# usb_interface.net
KiCad netlist of a schematic drawn in Altium Designer
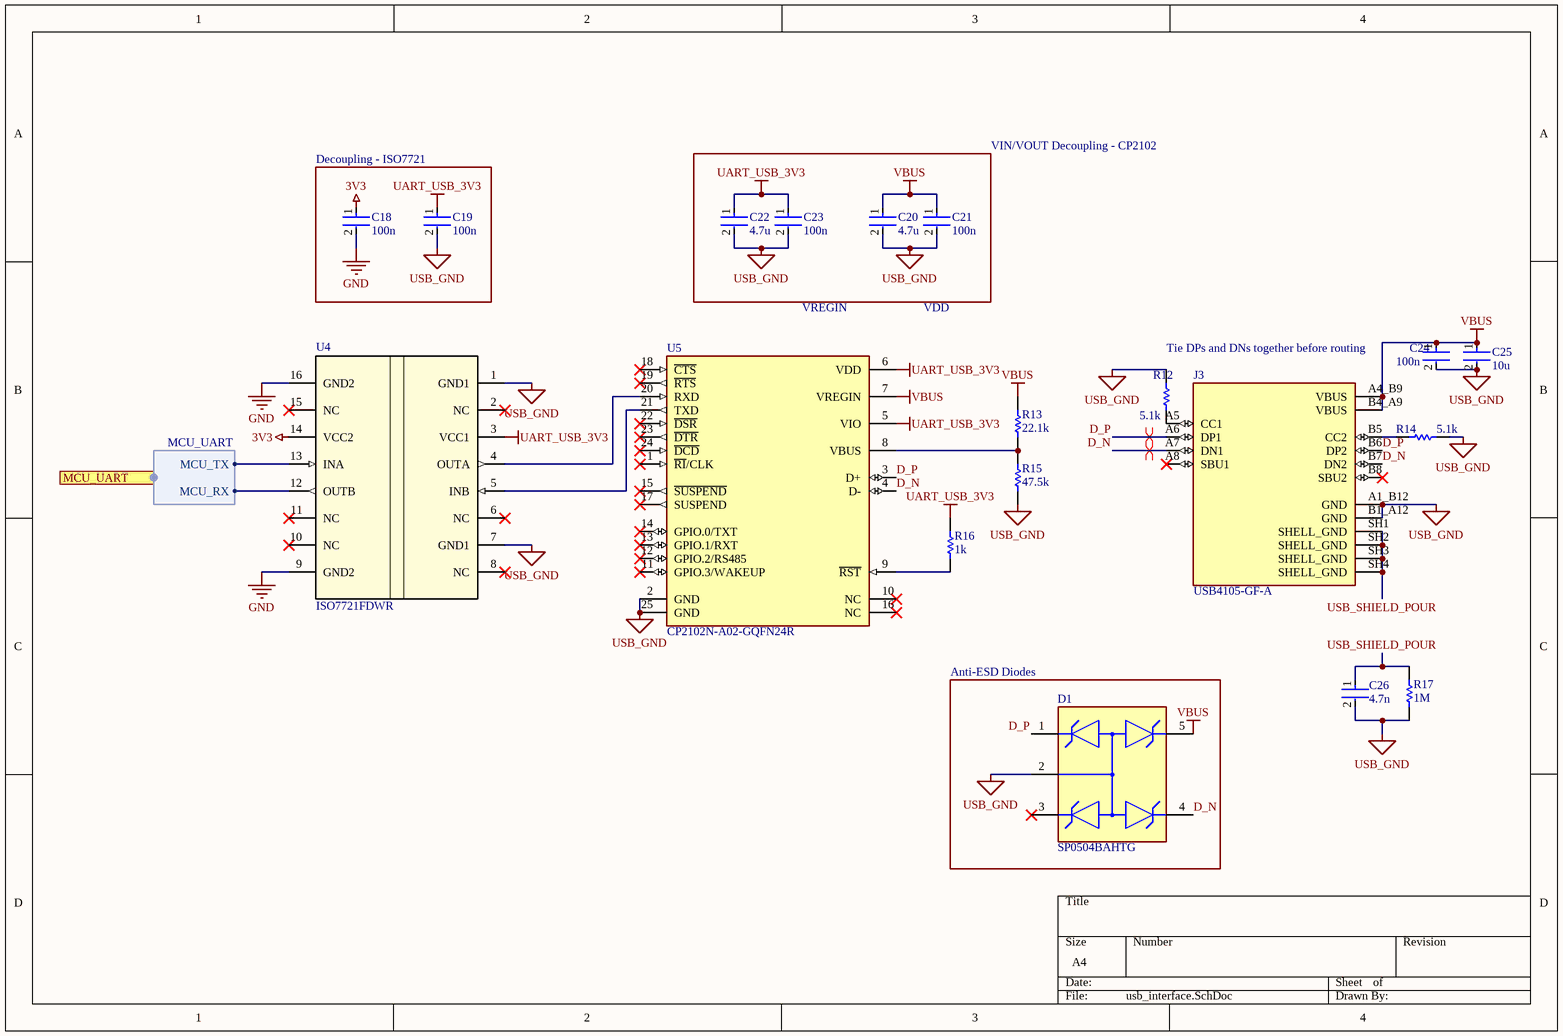
[diagram p0: usb_interface.SchDoc]

(export (version "E")
  (design (tool "Eeschema 10.0.6"))
  (components
    (comp (ref "C18")
      (value "100n")
      (footprint "C_IM 0603")
      (description "Multilayer Ceramic Capacitor, CC Series, 0.1 - F, - 10%, X7R, 50 V, 0603 [1608 Metric]")
      (fields
        (field (name "MANUFACTURER") "Yageo Group")
        (field (name "MANUFACTURER PART NUMBER") "CC0603KRX7R9BB104")
      )
      (libsource (lib "Schlib1") (part "CC0603KRX7R9BB104"))
    )
    (comp (ref "C19")
      (value "100n")
      (footprint "C_IM 0603")
      (description "Multilayer Ceramic Capacitor, CC Series, 0.1 - F, - 10%, X7R, 50 V, 0603 [1608 Metric]")
      (fields
        (field (name "MANUFACTURER") "Yageo Group")
        (field (name "MANUFACTURER PART NUMBER") "CC0603KRX7R9BB104")
      )
      (libsource (lib "Schlib1") (part "CC0603KRX7R9BB104"))
    )
    (comp (ref "C20")
      (value "4.7u")
      (footprint "C_IM 0805")
      (description "Surface Mount Ceramic Multilayer Capacitor 4.7uF 10% X5R 6.3V 0805 Blister T/R")
      (fields
        (field (name "MANUFACTURER") "Yageo Group")
        (field (name "MANUFACTURER PART NUMBER") "CC0805KKX5R5BB475")
      )
      (libsource (lib "Schlib1") (part "CC0805KKX5R5BB475"))
    )
    (comp (ref "C21")
      (value "100n")
      (footprint "C_IM 0603")
      (description "Multilayer Ceramic Capacitor, CC Series, 0.1 - F, - 10%, X7R, 50 V, 0603 [1608 Metric]")
      (fields
        (field (name "MANUFACTURER") "Yageo Group")
        (field (name "MANUFACTURER PART NUMBER") "CC0603KRX7R9BB104")
      )
      (libsource (lib "Schlib1") (part "CC0603KRX7R9BB104"))
    )
    (comp (ref "C22")
      (value "4.7u")
      (footprint "C_IM 0805")
      (description "Surface Mount Ceramic Multilayer Capacitor 4.7uF 10% X5R 6.3V 0805 Blister T/R")
      (fields
        (field (name "MANUFACTURER") "Yageo Group")
        (field (name "MANUFACTURER PART NUMBER") "CC0805KKX5R5BB475")
      )
      (libsource (lib "Schlib1") (part "CC0805KKX5R5BB475"))
    )
    (comp (ref "C23")
      (value "100n")
      (footprint "C_IM 0603")
      (description "Multilayer Ceramic Capacitor, CC Series, 0.1 - F, - 10%, X7R, 50 V, 0603 [1608 Metric]")
      (fields
        (field (name "MANUFACTURER") "Yageo Group")
        (field (name "MANUFACTURER PART NUMBER") "CC0603KRX7R9BB104")
      )
      (libsource (lib "Schlib1") (part "CC0603KRX7R9BB104"))
    )
    (comp (ref "C24")
      (value "100n")
      (footprint "C_IM 0603")
      (description "Multilayer Ceramic Capacitor, CC Series, 0.1 - F, - 10%, X7R, 50 V, 0603 [1608 Metric]")
      (fields
        (field (name "MANUFACTURER") "Yageo Group")
        (field (name "MANUFACTURER PART NUMBER") "CC0603KRX7R9BB104")
      )
      (libsource (lib "Schlib1") (part "CC0603KRX7R9BB104"))
    )
    (comp (ref "C25")
      (value "10u")
      (footprint "C_IM 0603")
      (description "Multilayer Ceramic Capacitors MLCC – SMD/SMT; YAGEO; CC0603MRX5R7BB106; 10 µF; 0603; 16 V; 16 V")
      (fields
        (field (name "MANUFACTURER") "Yageo Group")
        (field (name "MANUFACTURER PART NUMBER") "CC0603MRX5R7BB106")
      )
      (libsource (lib "Schlib1") (part "CC0603MRX5R7BB106"))
    )
    (comp (ref "C26")
      (value "4.7n")
      (footprint "C_IM 0805")
      (description "Cap Ceramic 0.0047uF 1000V X7R 10% Pad SMD 0805 125C Automotive AEC-Q200 Medical T/R")
      (fields
        (field (name "MANUFACTURER") "Yageo Group")
        (field (name "MANUFACTURER PART NUMBER") "C0805C472KDRACAUTO")
      )
      (libsource (lib "Schlib1") (part "C0805C472KDRACAUTO"))
    )
    (comp (ref "D1")
      (value "SP0504BAHTG")
      (footprint "SOT-23-5 Small")
      (description "SP050xBA Series 8 V 30 pF Uni-Directional SMT TVS Avalanche Diode Array SOT-23-5")
      (fields (field (name "MANUFACTURER") "Littelfuse"))
      (libsource (lib "Schlib1") (part "SP0504BAHTG"))
    )
    (comp (ref "J3")
      (value "USB4105-GF-A")
      (footprint "GCT_USB4105-GF-A")
      (description "USB Connector, 24 Contact(s), Female, Right Angle, Solder Terminal, Locking, Receptacle")
      (fields (field (name "MANUFACTURER") "Global Connector Technology"))
      (libsource (lib "Schlib1") (part "USB4105-GF-A"))
    )
    (comp (ref "R12")
      (value "5.1k")
      (footprint "R_IM 0805")
      (description "125Mw Thick Film Resistors 100Ppm/ 1% 5.1K 0805 Chip Resistor Surface Mount Rohs")
      (fields
        (field (name "MANUFACTURER") "Yageo Group")
        (field (name "MANUFACTURER PART NUMBER") "RC0805FR-075K1L")
      )
      (libsource (lib "Schlib1") (part "RC0805FR-075K1L"))
    )
    (comp (ref "R13")
      (value "22.1k")
      (footprint "R_IM 0805")
      (description "Res Thick Film 0805 22.1K Ohm 1% 0.125W(1/8W) ±100ppm/C Pad SMD T/R")
      (fields
        (field (name "MANUFACTURER") "Yageo Group")
        (field (name "MANUFACTURER PART NUMBER") "RC0805FR-0722K1L")
      )
      (libsource (lib "Schlib1") (part "RC0805FR-0722K1L"))
    )
    (comp (ref "R14")
      (value "5.1k")
      (footprint "R_IM 0805")
      (description "125Mw Thick Film Resistors 100Ppm/ 1% 5.1K 0805 Chip Resistor Surface Mount Rohs")
      (fields
        (field (name "MANUFACTURER") "Yageo Group")
        (field (name "MANUFACTURER PART NUMBER") "RC0805FR-075K1L")
      )
      (libsource (lib "Schlib1") (part "RC0805FR-075K1L"))
    )
    (comp (ref "R15")
      (value "47.5k")
      (footprint "R_IM 0805")
      (description "47.5 kOhms ±1% 0.125W, 1/8W Chip Resistor 0805 (2012 Metric) Moisture Resistant Thick Film")
      (fields
        (field (name "MANUFACTURER") "Yageo Group")
        (field (name "MANUFACTURER PART NUMBER") "RC0805FR-0747K5L")
      )
      (libsource (lib "Schlib1") (part "RC0805FR-0747K5L"))
    )
    (comp (ref "R16")
      (value "1k")
      (footprint "R_IM 0805")
      (description "Resistor, thick film, SMD 0805 (2012), 1 kΩ, 0.125 W, ±1 %, RC0805FR-071KL")
      (fields
        (field (name "MANUFACTURER") "Yageo Group")
        (field (name "MANUFACTURER PART NUMBER") "RC0805FR-071KL")
      )
      (libsource (lib "Schlib1") (part "RC0805FR-071KL"))
    )
    (comp (ref "R17")
      (value "1M")
      (footprint "R_IM 0805")
      (description "125mW Thick Film Resistors 150V ±100ppm/℃ ±1% 1MΩ 0805 Chip Resistor - Surface Mount ROHS")
      (fields
        (field (name "MANUFACTURER") "Yageo Group")
        (field (name "MANUFACTURER PART NUMBER") "RC0805FR-071ML")
      )
      (libsource (lib "Schlib1") (part "RC0805FR-071ML"))
    )
    (comp (ref "U4")
      (value "ISO7721FDWR")
      (footprint "16-SOIC")
      (description "Robust EMC, dual-channel, 1/1, reinforced digital isolator 16-SOIC -55 to 125")
      (fields (field (name "MANUFACTURER") "Texas Instruments"))
      (libsource (lib "high_voltage_controller") (part "ISO7721FDWR"))
    )
    (comp (ref "U5")
      (value "CP2102N-A02-GQFN24R")
      (footprint "24-VFQFN")
      (description "IC Usb to Uart Bridge QFN24 / Usb Bridge, Usb to Uart Usb 2.0 Uart Interface 24-QFN (4X4)")
      (fields (field (name "MANUFACTURER") "Silicon Lab"))
      (libsource (lib "high_voltage_controller") (part "CP2102N-A02-GQFN24R"))
    )
  )
  (nets
    (net (code "2") (name "/D_N") (class "Default")
      (node (ref "D1") (pin "4") (pinfunction "4_4") (pintype "passive"))
      (node (ref "J3") (pin "A7") (pinfunction "DN1_A7") (pintype "bidirectional"))
      (node (ref "J3") (pin "B7") (pinfunction "DN2_B7") (pintype "bidirectional"))
      (node (ref "U5") (pin "4") (pinfunction "D-_4") (pintype "bidirectional"))
    )
    (net (code "3") (name "/D_P") (class "Default")
      (node (ref "D1") (pin "1") (pinfunction "1_1") (pintype "passive"))
      (node (ref "J3") (pin "A6") (pinfunction "DP1_A6") (pintype "bidirectional"))
      (node (ref "J3") (pin "B6") (pinfunction "DP2_B6") (pintype "bidirectional"))
      (node (ref "U5") (pin "3") (pinfunction "D+_3") (pintype "bidirectional"))
    )
    (net (code "4") (name "/MCU_RX") (class "Default")
      (node (ref "U4") (pin "12") (pinfunction "OUTB_12") (pintype "output"))
    )
    (net (code "5") (name "/MCU_TX") (class "Default")
      (node (ref "U4") (pin "13") (pinfunction "INA_13") (pintype "input"))
    )
    (net (code "6") (name "/USB_SHIELD_POUR") (class "Default")
      (node (ref "C26") (pin "1") (pinfunction "1_1") (pintype "passive"))
      (node (ref "J3") (pin "SH1") (pinfunction "SHELL_GND_SH1") (pintype "power_in"))
      (node (ref "J3") (pin "SH2") (pinfunction "SHELL_GND_SH2") (pintype "power_in"))
      (node (ref "J3") (pin "SH3") (pinfunction "SHELL_GND_SH3") (pintype "power_in"))
      (node (ref "J3") (pin "SH4") (pinfunction "SHELL_GND_SH4") (pintype "power_in"))
      (node (ref "R17") (pin "2") (pinfunction "2_2") (pintype "passive"))
    )
    (net (code "8") (name "3V3") (class "Default")
      (node (ref "C18") (pin "1") (pinfunction "1_1") (pintype "passive"))
      (node (ref "U4") (pin "14") (pinfunction "VCC2_14") (pintype "power_in"))
    )
    (net (code "9") (name "GND") (class "Default")
      (node (ref "C18") (pin "2") (pinfunction "2_2") (pintype "passive"))
      (node (ref "U4") (pin "16") (pinfunction "GND2_16") (pintype "power_in"))
      (node (ref "U4") (pin "9") (pinfunction "GND2_9") (pintype "power_in"))
    )
    (net (code "10") (name "Net-(J3-CC1)") (class "Default")
      (node (ref "J3") (pin "A5") (pinfunction "CC1_A5") (pintype "bidirectional"))
      (node (ref "R12") (pin "2") (pinfunction "2_2") (pintype "passive"))
    )
    (net (code "11") (name "Net-(J3-CC2)") (class "Default")
      (node (ref "J3") (pin "B5") (pinfunction "CC2_B5") (pintype "bidirectional"))
      (node (ref "R14") (pin "1") (pinfunction "1_1") (pintype "passive"))
    )
    (net (code "12") (name "Net-(U4-INB)") (class "Default")
      (node (ref "U4") (pin "5") (pinfunction "INB_5") (pintype "input"))
      (node (ref "U5") (pin "21") (pinfunction "TXD_21") (pintype "output"))
    )
    (net (code "13") (name "Net-(U4-OUTA)") (class "Default")
      (node (ref "U4") (pin "4") (pinfunction "OUTA_4") (pintype "output"))
      (node (ref "U5") (pin "20") (pinfunction "RXD_20") (pintype "input"))
    )
    (net (code "14") (name "Net-(U5-VBUS)") (class "Default")
      (node (ref "R13") (pin "1") (pinfunction "1_1") (pintype "passive"))
      (node (ref "R15") (pin "2") (pinfunction "2_2") (pintype "passive"))
      (node (ref "U5") (pin "8") (pinfunction "VBUS_8") (pintype "power_in"))
    )
    (net (code "15") (name "Net-(U5-~{RST})") (class "Default")
      (node (ref "R16") (pin "1") (pinfunction "1_1") (pintype "passive"))
      (node (ref "U5") (pin "9") (pinfunction "~{RST}_9") (pintype "input"))
    )
    (net (code "16") (name "UART_USB_3V3") (class "Default")
      (node (ref "C19") (pin "1") (pinfunction "1_1") (pintype "passive"))
      (node (ref "C22") (pin "1") (pinfunction "1_1") (pintype "passive"))
      (node (ref "C23") (pin "1") (pinfunction "1_1") (pintype "passive"))
      (node (ref "R16") (pin "2") (pinfunction "2_2") (pintype "passive"))
      (node (ref "U4") (pin "3") (pinfunction "VCC1_3") (pintype "power_in"))
      (node (ref "U5") (pin "5") (pinfunction "VIO_5") (pintype "power_in"))
      (node (ref "U5") (pin "6") (pinfunction "VDD_6") (pintype "power_in"))
    )
    (net (code "17") (name "USB_GND") (class "Default")
      (node (ref "C19") (pin "2") (pinfunction "2_2") (pintype "passive"))
      (node (ref "C20") (pin "2") (pinfunction "2_2") (pintype "passive"))
      (node (ref "C21") (pin "2") (pinfunction "2_2") (pintype "passive"))
      (node (ref "C22") (pin "2") (pinfunction "2_2") (pintype "passive"))
      (node (ref "C23") (pin "2") (pinfunction "2_2") (pintype "passive"))
      (node (ref "C24") (pin "2") (pinfunction "2_2") (pintype "passive"))
      (node (ref "C25") (pin "2") (pinfunction "2_2") (pintype "passive"))
      (node (ref "C26") (pin "2") (pinfunction "2_2") (pintype "passive"))
      (node (ref "D1") (pin "2") (pinfunction "2_2") (pintype "passive"))
      (node (ref "J3") (pin "A1_B12") (pinfunction "GND_A1_B12") (pintype "power_in"))
      (node (ref "J3") (pin "B1_A12") (pinfunction "GND_B1_A12") (pintype "power_in"))
      (node (ref "R12") (pin "1") (pinfunction "1_1") (pintype "passive"))
      (node (ref "R14") (pin "2") (pinfunction "2_2") (pintype "passive"))
      (node (ref "R15") (pin "1") (pinfunction "1_1") (pintype "passive"))
      (node (ref "R17") (pin "1") (pinfunction "1_1") (pintype "passive"))
      (node (ref "U4") (pin "1") (pinfunction "GND1_1") (pintype "power_in"))
      (node (ref "U4") (pin "7") (pinfunction "GND1_7") (pintype "power_in"))
      (node (ref "U5") (pin "2") (pinfunction "GND_2") (pintype "power_in"))
      (node (ref "U5") (pin "25") (pinfunction "GND_25") (pintype "power_in"))
    )
    (net (code "18") (name "VBUS") (class "Default")
      (node (ref "C20") (pin "1") (pinfunction "1_1") (pintype "passive"))
      (node (ref "C21") (pin "1") (pinfunction "1_1") (pintype "passive"))
      (node (ref "C24") (pin "1") (pinfunction "1_1") (pintype "passive"))
      (node (ref "C25") (pin "1") (pinfunction "1_1") (pintype "passive"))
      (node (ref "D1") (pin "5") (pinfunction "5_5") (pintype "passive"))
      (node (ref "J3") (pin "A4_B9") (pinfunction "VBUS_A4_B9") (pintype "power_in"))
      (node (ref "J3") (pin "B4_A9") (pinfunction "VBUS_B4_A9") (pintype "power_in"))
      (node (ref "R13") (pin "2") (pinfunction "2_2") (pintype "passive"))
      (node (ref "U5") (pin "7") (pinfunction "VREGIN_7") (pintype "power_in"))
    )
    (net (code "19") (name "unconnected-(D1-Pad3)") (class "Default")
      (node (ref "D1") (pin "3") (pinfunction "3_3") (pintype "passive+no_connect"))
    )
    (net (code "20") (name "unconnected-(J3-SBU1-PadA8)") (class "Default")
      (node (ref "J3") (pin "A8") (pinfunction "SBU1_A8") (pintype "bidirectional+no_connect"))
    )
    (net (code "21") (name "unconnected-(J3-SBU2-PadB8)") (class "Default")
      (node (ref "J3") (pin "B8") (pinfunction "SBU2_B8") (pintype "bidirectional+no_connect"))
    )
    (net (code "22") (name "unconnected-(U4-NC-Pad2)") (class "Default")
      (node (ref "U4") (pin "2") (pinfunction "NC_2") (pintype "passive+no_connect"))
    )
    (net (code "23") (name "unconnected-(U4-NC-Pad6)") (class "Default")
      (node (ref "U4") (pin "6") (pinfunction "NC_6") (pintype "passive+no_connect"))
    )
    (net (code "24") (name "unconnected-(U4-NC-Pad8)") (class "Default")
      (node (ref "U4") (pin "8") (pinfunction "NC_8") (pintype "passive+no_connect"))
    )
    (net (code "25") (name "unconnected-(U4-NC-Pad10)") (class "Default")
      (node (ref "U4") (pin "10") (pinfunction "NC_10") (pintype "passive+no_connect"))
    )
    (net (code "26") (name "unconnected-(U4-NC-Pad11)") (class "Default")
      (node (ref "U4") (pin "11") (pinfunction "NC_11") (pintype "passive+no_connect"))
    )
    (net (code "27") (name "unconnected-(U4-NC-Pad15)") (class "Default")
      (node (ref "U4") (pin "15") (pinfunction "NC_15") (pintype "passive+no_connect"))
    )
    (net (code "28") (name "unconnected-(U5-GPIO.0{slash}TXT-Pad14)") (class "Default")
      (node (ref "U5") (pin "14") (pinfunction "GPIO.0/TXT_14") (pintype "bidirectional+no_connect"))
    )
    (net (code "29") (name "unconnected-(U5-GPIO.1{slash}RXT-Pad13)") (class "Default")
      (node (ref "U5") (pin "13") (pinfunction "GPIO.1/RXT_13") (pintype "bidirectional+no_connect"))
    )
    (net (code "30") (name "unconnected-(U5-GPIO.2{slash}RS485-Pad12)") (class "Default")
      (node (ref "U5") (pin "12") (pinfunction "GPIO.2/RS485_12") (pintype "bidirectional+no_connect"))
    )
    (net (code "31") (name "unconnected-(U5-GPIO.3{slash}WAKEUP-Pad11)") (class "Default")
      (node (ref "U5") (pin "11") (pinfunction "GPIO.3/WAKEUP_11") (pintype "bidirectional+no_connect"))
    )
    (net (code "32") (name "unconnected-(U5-NC-Pad10)") (class "Default")
      (node (ref "U5") (pin "10") (pinfunction "NC_10") (pintype "passive+no_connect"))
    )
    (net (code "33") (name "unconnected-(U5-NC-Pad16)") (class "Default")
      (node (ref "U5") (pin "16") (pinfunction "NC_16") (pintype "passive+no_connect"))
    )
    (net (code "34") (name "unconnected-(U5-SUSPEND-Pad17)") (class "Default")
      (node (ref "U5") (pin "17") (pinfunction "SUSPEND_17") (pintype "output+no_connect"))
    )
    (net (code "35") (name "unconnected-(U5-~{CTS}-Pad18)") (class "Default")
      (node (ref "U5") (pin "18") (pinfunction "~{CTS}_18") (pintype "input+no_connect"))
    )
    (net (code "36") (name "unconnected-(U5-~{DCD}-Pad24)") (class "Default")
      (node (ref "U5") (pin "24") (pinfunction "~{DCD}_24") (pintype "input+no_connect"))
    )
    (net (code "37") (name "unconnected-(U5-~{DSR}-Pad22)") (class "Default")
      (node (ref "U5") (pin "22") (pinfunction "~{DSR}_22") (pintype "input+no_connect"))
    )
    (net (code "38") (name "unconnected-(U5-~{DTR}-Pad23)") (class "Default")
      (node (ref "U5") (pin "23") (pinfunction "~{DTR}_23") (pintype "output+no_connect"))
    )
    (net (code "39") (name "unconnected-(U5-~{RI}{slash}CLK-Pad1)") (class "Default")
      (node (ref "U5") (pin "1") (pinfunction "~{RI}/CLK_1") (pintype "input+no_connect"))
    )
    (net (code "40") (name "unconnected-(U5-~{RTS}-Pad19)") (class "Default")
      (node (ref "U5") (pin "19") (pinfunction "~{RTS}_19") (pintype "output+no_connect"))
    )
    (net (code "41") (name "unconnected-(U5-~{SUSPEND}-Pad15)") (class "Default")
      (node (ref "U5") (pin "15") (pinfunction "~{SUSPEND}_15") (pintype "output+no_connect"))
    )
  )
)
